# V1.net
KiCad netlist of a schematic drawn in EAGLE
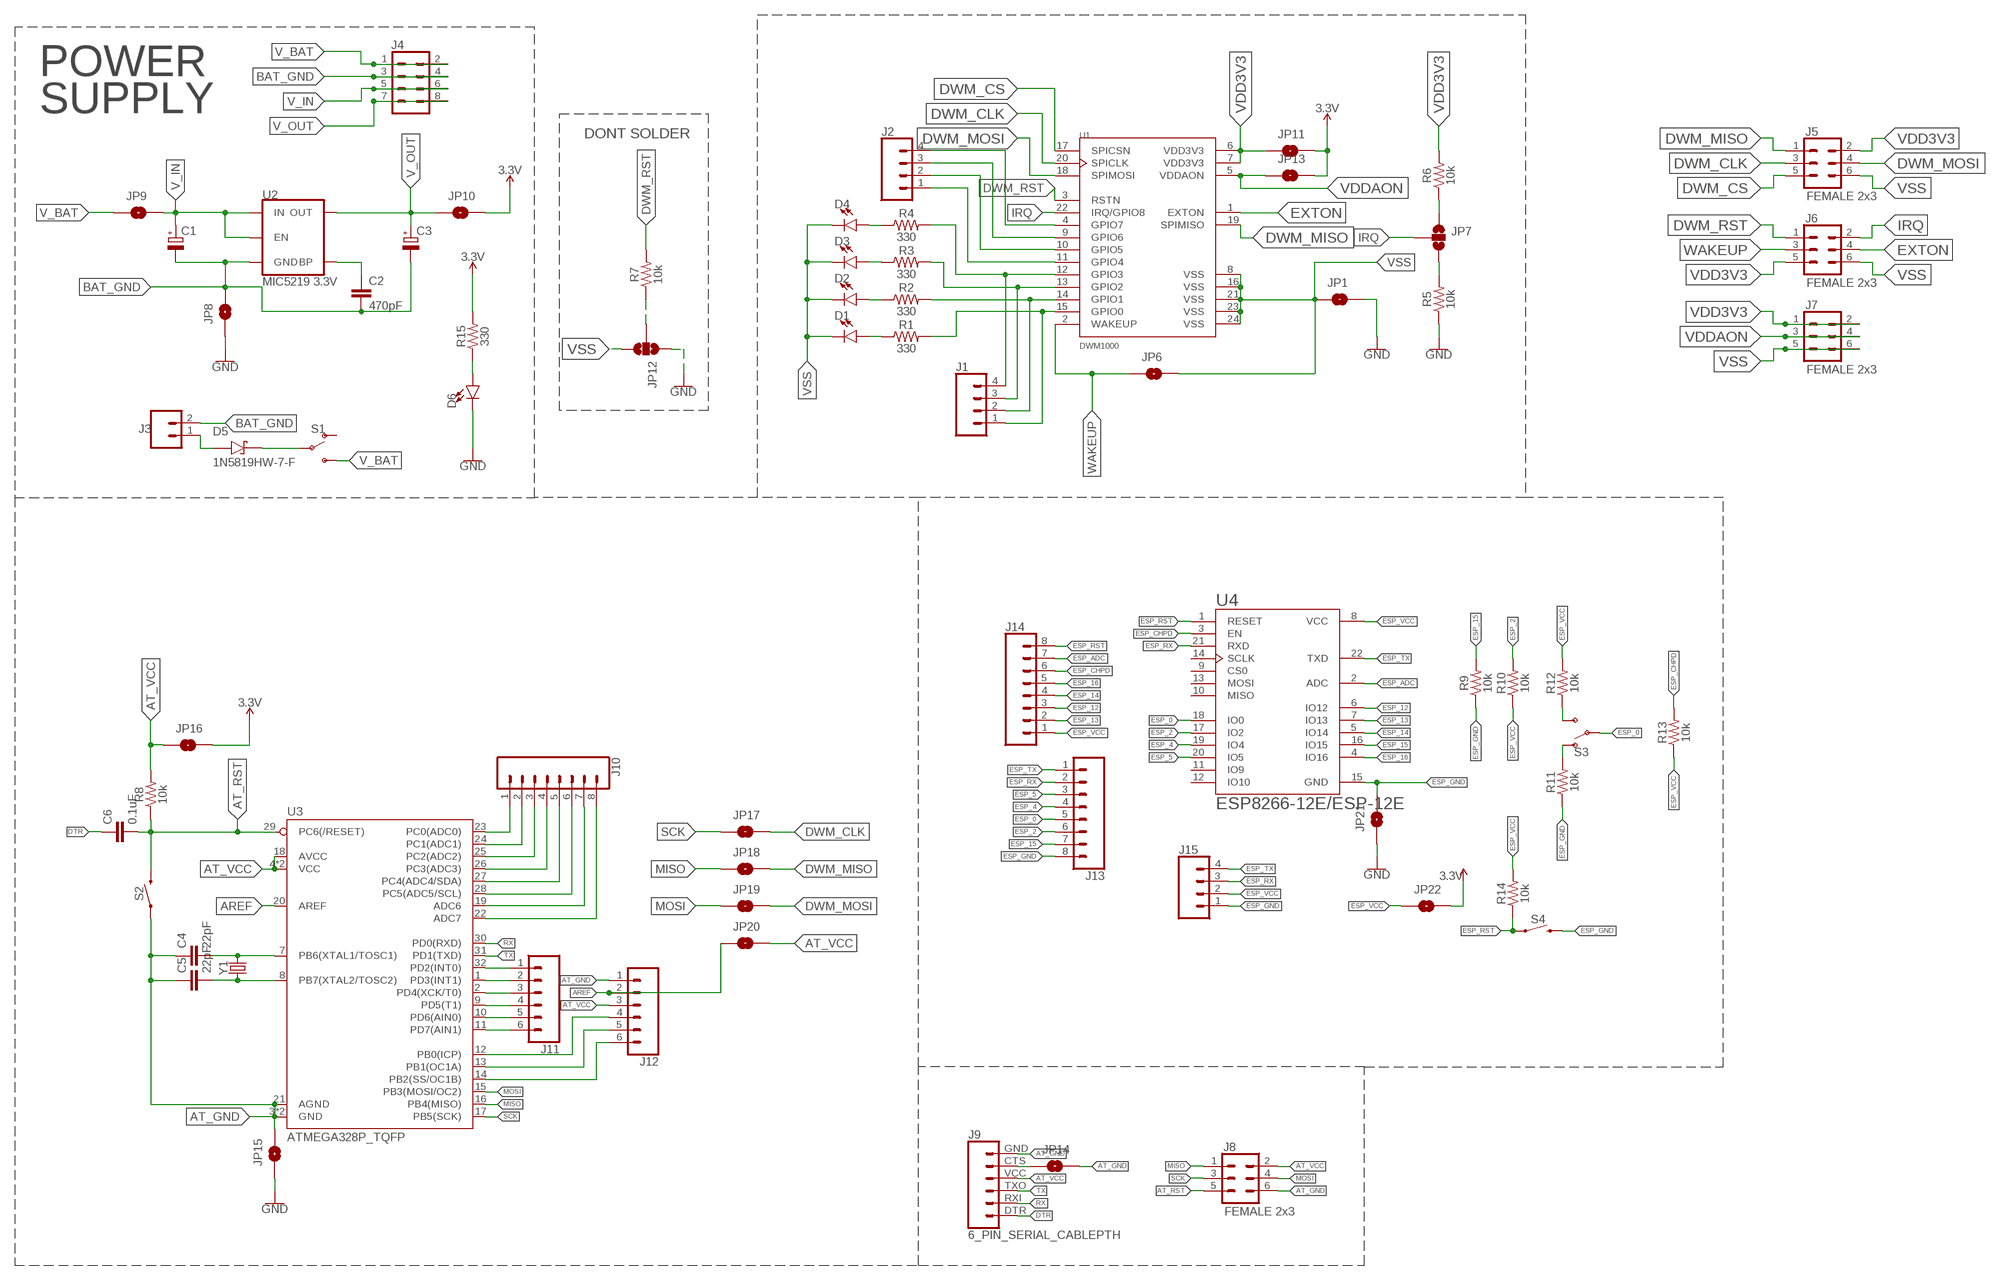
[diagram p0: schematic, sheet 1]

(export (version "E")
  (design (tool "Eeschema 10.0.6"))
  (components
    (comp (ref "C1")
      (value "CPOL-EUSMCA")
      (footprint "eagle-import:SMC_A")
      (libsource (lib "eagle-import") (part "CPOL-EUSMCA"))
    )
    (comp (ref "C2")
      (value "470pF")
      (footprint "eagle-import:0603")
      (libsource (lib "eagle-import") (part "470PF-0603-50V-5%"))
    )
    (comp (ref "C3")
      (value "CPOL-EUSMCA")
      (footprint "eagle-import:SMC_A")
      (libsource (lib "eagle-import") (part "CPOL-EUSMCA"))
    )
    (comp (ref "C4")
      (value "22pF")
      (footprint "eagle-import:0603")
      (libsource (lib "eagle-import") (part "22PF-0603-50V-5%"))
    )
    (comp (ref "C5")
      (value "22pF")
      (footprint "eagle-import:0603")
      (libsource (lib "eagle-import") (part "22PF-0603-50V-5%"))
    )
    (comp (ref "C6")
      (value "0.1uF")
      (footprint "eagle-import:0603")
      (libsource (lib "eagle-import") (part "0.1UF-0603-25V-(+80/-20%)"))
    )
    (comp (ref "D1")
      (value "LED0603")
      (footprint "eagle-import:LED-0603")
      (libsource (lib "eagle-import") (part "LED0603"))
    )
    (comp (ref "D2")
      (value "LED0603")
      (footprint "eagle-import:LED-0603")
      (libsource (lib "eagle-import") (part "LED0603"))
    )
    (comp (ref "D3")
      (value "LED0603")
      (footprint "eagle-import:LED-0603")
      (libsource (lib "eagle-import") (part "LED0603"))
    )
    (comp (ref "D4")
      (value "LED0603")
      (footprint "eagle-import:LED-0603")
      (libsource (lib "eagle-import") (part "LED0603"))
    )
    (comp (ref "D5")
      (value "1N5819HW-7-F")
      (footprint "eagle-import:SOD3715X145N")
      (fields (field (name "MF") "Diodes Inc."))
      (libsource (lib "eagle-import") (part "1N5819HW-7-F"))
    )
    (comp (ref "D6")
      (value "LED0603")
      (footprint "eagle-import:LED-0603")
      (libsource (lib "eagle-import") (part "LED0603"))
    )
    (comp (ref "J1")
      (value "CONN_04")
      (footprint "eagle-import:1X04")
      (libsource (lib "eagle-import") (part "CONN_04"))
    )
    (comp (ref "J2")
      (value "CONN_04")
      (footprint "eagle-import:1X04")
      (libsource (lib "eagle-import") (part "CONN_04"))
    )
    (comp (ref "J3")
      (value "CONN_02")
      (footprint "eagle-import:1X02")
      (libsource (lib "eagle-import") (part "CONN_02"))
    )
    (comp (ref "J4")
      (value "CONN_04X2")
      (footprint "eagle-import:2X4")
      (libsource (lib "eagle-import") (part "CONN_04X2"))
    )
    (comp (ref "J5")
      (value "FEMALE 2x3")
      (footprint "eagle-import:2X3")
      (libsource (lib "eagle-import") (part "CONN_03X2FEMALE"))
    )
    (comp (ref "J6")
      (value "FEMALE 2x3")
      (footprint "eagle-import:2X3")
      (libsource (lib "eagle-import") (part "CONN_03X2FEMALE"))
    )
    (comp (ref "J7")
      (value "FEMALE 2x3")
      (footprint "eagle-import:2X3")
      (libsource (lib "eagle-import") (part "CONN_03X2FEMALE"))
    )
    (comp (ref "J8")
      (value "FEMALE 2x3")
      (footprint "eagle-import:2X3")
      (libsource (lib "eagle-import") (part "CONN_03X2FEMALE"))
    )
    (comp (ref "J9")
      (value "6_PIN_SERIAL_CABLEPTH")
      (footprint "eagle-import:FTDI_BASIC")
      (libsource (lib "eagle-import") (part "6_PIN_SERIAL_CABLEPTH"))
    )
    (comp (ref "J10")
      (value "CONN_08\"")
      (footprint "eagle-import:1X08")
      (libsource (lib "eagle-import") (part "CONN_08{dblquote}"))
    )
    (comp (ref "J11")
      (value "CONN_06SILK_FEMALE_PTH")
      (footprint "eagle-import:1X06")
      (libsource (lib "eagle-import") (part "CONN_06SILK_FEMALE_PTH"))
    )
    (comp (ref "J12")
      (value "CONN_06SILK_FEMALE_PTH")
      (footprint "eagle-import:1X06")
      (libsource (lib "eagle-import") (part "CONN_06SILK_FEMALE_PTH"))
    )
    (comp (ref "J13")
      (value "CONN_08\"")
      (footprint "eagle-import:1X08")
      (libsource (lib "eagle-import") (part "CONN_08{dblquote}"))
    )
    (comp (ref "J14")
      (value "CONN_08\"")
      (footprint "eagle-import:1X08")
      (libsource (lib "eagle-import") (part "CONN_08{dblquote}"))
    )
    (comp (ref "J15")
      (value "CONN_04")
      (footprint "eagle-import:1X04")
      (libsource (lib "eagle-import") (part "CONN_04"))
    )
    (comp (ref "JP1")
      (value "JUMPER-SMT_2_NO_NO-SILK")
      (footprint "eagle-import:SMT-JUMPER_2_NO_NO-SILK")
      (libsource (lib "eagle-import") (part "JUMPER-SMT_2_NO_NO-SILK"))
    )
    (comp (ref "JP6")
      (value "JUMPER-SMT_2_NO_NO-SILK")
      (footprint "eagle-import:SMT-JUMPER_2_NO_NO-SILK")
      (libsource (lib "eagle-import") (part "JUMPER-SMT_2_NO_NO-SILK"))
    )
    (comp (ref "JP7")
      (value "JUMPER-SMT_3_NO_NO_SILK")
      (footprint "eagle-import:SMT-JUMPER_3_0-NO_TRACE_NO-SILK")
      (libsource (lib "eagle-import") (part "JUMPER-SMT_3_NO_NO_SILK"))
    )
    (comp (ref "JP8")
      (value "JUMPER-SMT_2_NO_NO-SILK")
      (footprint "eagle-import:SMT-JUMPER_2_NO_NO-SILK")
      (libsource (lib "eagle-import") (part "JUMPER-SMT_2_NO_NO-SILK"))
    )
    (comp (ref "JP9")
      (value "JUMPER-SMT_2_NO_NO-SILK")
      (footprint "eagle-import:SMT-JUMPER_2_NO_NO-SILK")
      (libsource (lib "eagle-import") (part "JUMPER-SMT_2_NO_NO-SILK"))
    )
    (comp (ref "JP10")
      (value "JUMPER-SMT_2_NO_NO-SILK")
      (footprint "eagle-import:SMT-JUMPER_2_NO_NO-SILK")
      (libsource (lib "eagle-import") (part "JUMPER-SMT_2_NO_NO-SILK"))
    )
    (comp (ref "JP11")
      (value "JUMPER-SMT_2_NO_NO-SILK")
      (footprint "eagle-import:SMT-JUMPER_2_NO_NO-SILK")
      (libsource (lib "eagle-import") (part "JUMPER-SMT_2_NO_NO-SILK"))
    )
    (comp (ref "JP12")
      (value "JUMPER-SMT_3_NO_NO_SILK")
      (footprint "eagle-import:SMT-JUMPER_3_0-NO_TRACE_NO-SILK")
      (libsource (lib "eagle-import") (part "JUMPER-SMT_3_NO_NO_SILK"))
    )
    (comp (ref "JP13")
      (value "JUMPER-SMT_2_NO_NO-SILK")
      (footprint "eagle-import:SMT-JUMPER_2_NO_NO-SILK")
      (libsource (lib "eagle-import") (part "JUMPER-SMT_2_NO_NO-SILK"))
    )
    (comp (ref "JP14")
      (value "JUMPER-SMT_2_NO_NO-SILK")
      (footprint "eagle-import:SMT-JUMPER_2_NO_NO-SILK")
      (libsource (lib "eagle-import") (part "JUMPER-SMT_2_NO_NO-SILK"))
    )
    (comp (ref "JP15")
      (value "JUMPER-SMT_2_NO_NO-SILK")
      (footprint "eagle-import:SMT-JUMPER_2_NO_NO-SILK")
      (libsource (lib "eagle-import") (part "JUMPER-SMT_2_NO_NO-SILK"))
    )
    (comp (ref "JP16")
      (value "JUMPER-SMT_2_NO_NO-SILK")
      (footprint "eagle-import:SMT-JUMPER_2_NO_NO-SILK")
      (libsource (lib "eagle-import") (part "JUMPER-SMT_2_NO_NO-SILK"))
    )
    (comp (ref "JP17")
      (value "JUMPER-SMT_2_NO_NO-SILK")
      (footprint "eagle-import:SMT-JUMPER_2_NO_NO-SILK")
      (libsource (lib "eagle-import") (part "JUMPER-SMT_2_NO_NO-SILK"))
    )
    (comp (ref "JP18")
      (value "JUMPER-SMT_2_NO_NO-SILK")
      (footprint "eagle-import:SMT-JUMPER_2_NO_NO-SILK")
      (libsource (lib "eagle-import") (part "JUMPER-SMT_2_NO_NO-SILK"))
    )
    (comp (ref "JP19")
      (value "JUMPER-SMT_2_NO_NO-SILK")
      (footprint "eagle-import:SMT-JUMPER_2_NO_NO-SILK")
      (libsource (lib "eagle-import") (part "JUMPER-SMT_2_NO_NO-SILK"))
    )
    (comp (ref "JP20")
      (value "JUMPER-SMT_2_NO_NO-SILK")
      (footprint "eagle-import:SMT-JUMPER_2_NO_NO-SILK")
      (libsource (lib "eagle-import") (part "JUMPER-SMT_2_NO_NO-SILK"))
    )
    (comp (ref "JP21")
      (value "JUMPER-SMT_2_NO_NO-SILK")
      (footprint "eagle-import:SMT-JUMPER_2_NO_NO-SILK")
      (libsource (lib "eagle-import") (part "JUMPER-SMT_2_NO_NO-SILK"))
    )
    (comp (ref "JP22")
      (value "JUMPER-SMT_2_NO_NO-SILK")
      (footprint "eagle-import:SMT-JUMPER_2_NO_NO-SILK")
      (libsource (lib "eagle-import") (part "JUMPER-SMT_2_NO_NO-SILK"))
    )
    (comp (ref "R1")
      (value "330")
      (footprint "eagle-import:0603")
      (libsource (lib "eagle-import") (part "330OHM-0603-1/10W-1%"))
    )
    (comp (ref "R2")
      (value "330")
      (footprint "eagle-import:0603")
      (libsource (lib "eagle-import") (part "330OHM-0603-1/10W-1%"))
    )
    (comp (ref "R3")
      (value "330")
      (footprint "eagle-import:0603")
      (libsource (lib "eagle-import") (part "330OHM-0603-1/10W-1%"))
    )
    (comp (ref "R4")
      (value "330")
      (footprint "eagle-import:0603")
      (libsource (lib "eagle-import") (part "330OHM-0603-1/10W-1%"))
    )
    (comp (ref "R5")
      (value "10k")
      (footprint "eagle-import:0603")
      (libsource (lib "eagle-import") (part "10KOHM-0603-1/10W-1%"))
    )
    (comp (ref "R6")
      (value "10k")
      (footprint "eagle-import:0603")
      (libsource (lib "eagle-import") (part "10KOHM-0603-1/10W-1%"))
    )
    (comp (ref "R7")
      (value "10k")
      (footprint "eagle-import:0603")
      (libsource (lib "eagle-import") (part "10KOHM-0603-1/10W-1%"))
    )
    (comp (ref "R8")
      (value "10k")
      (footprint "eagle-import:0603")
      (libsource (lib "eagle-import") (part "10KOHM-0603-1/10W-1%"))
    )
    (comp (ref "R9")
      (value "10k")
      (footprint "eagle-import:0603")
      (libsource (lib "eagle-import") (part "10KOHM-0603-1/10W-1%"))
    )
    (comp (ref "R10")
      (value "10k")
      (footprint "eagle-import:0603")
      (libsource (lib "eagle-import") (part "10KOHM-0603-1/10W-1%"))
    )
    (comp (ref "R11")
      (value "10k")
      (footprint "eagle-import:0603")
      (libsource (lib "eagle-import") (part "10KOHM-0603-1/10W-1%"))
    )
    (comp (ref "R12")
      (value "10k")
      (footprint "eagle-import:0603")
      (libsource (lib "eagle-import") (part "10KOHM-0603-1/10W-1%"))
    )
    (comp (ref "R13")
      (value "10k")
      (footprint "eagle-import:0603")
      (libsource (lib "eagle-import") (part "10KOHM-0603-1/10W-1%"))
    )
    (comp (ref "R14")
      (value "10k")
      (footprint "eagle-import:0603")
      (libsource (lib "eagle-import") (part "10KOHM-0603-1/10W-1%"))
    )
    (comp (ref "R15")
      (value "330")
      (footprint "eagle-import:0603")
      (libsource (lib "eagle-import") (part "330OHM-0603-1/10W-1%"))
    )
    (comp (ref "S1")
      (value "SWITCH-SPDT-SMD-AYZ0202")
      (footprint "eagle-import:SWITCH_DPDT_SMD_AYZ0202")
      (libsource (lib "eagle-import") (part "SWITCH-SPDT-SMD-AYZ0202"))
    )
    (comp (ref "S2")
      (value "MOMENTARY-SWITCH-SPST-SMD-6.0X3.5MM")
      (footprint "eagle-import:TACTILE_SWITCH_SMD_6.0X3.5MM")
      (libsource (lib "eagle-import") (part "MOMENTARY-SWITCH-SPST-SMD-6.0X3.5MM"))
    )
    (comp (ref "S3")
      (value "SWITCH-SPDT-SMD-AYZ0202")
      (footprint "eagle-import:SWITCH_DPDT_SMD_AYZ0202")
      (libsource (lib "eagle-import") (part "SWITCH-SPDT-SMD-AYZ0202"))
    )
    (comp (ref "S4")
      (value "MOMENTARY-SWITCH-SPST-SMD-6.0X3.5MM")
      (footprint "eagle-import:TACTILE_SWITCH_SMD_6.0X3.5MM")
      (libsource (lib "eagle-import") (part "MOMENTARY-SWITCH-SPST-SMD-6.0X3.5MM"))
    )
    (comp (ref "U1")
      (value "DWM1000")
      (footprint "eagle-import:XCVR_DWM1000")
      (fields (field (name "MF") "Decawave Limited"))
      (libsource (lib "eagle-import") (part "DWM1000"))
    )
    (comp (ref "U2")
      (value "MIC5219 3.3V")
      (footprint "eagle-import:SOT23-5")
      (libsource (lib "eagle-import") (part "V_REG_MIC52193.3V"))
    )
    (comp (ref "U3")
      (value "ATMEGA328P_TQFP")
      (footprint "eagle-import:TQFP32-08")
      (libsource (lib "eagle-import") (part "ATMEGA328P_TQFP"))
    )
    (comp (ref "U4")
      (value "ESP8266-12E/ESP-12E")
      (footprint "eagle-import:XCVR_ESP8266-12E_ESP-12E")
      (fields (field (name "MF") "AI-Thinker"))
      (libsource (lib "eagle-import") (part "ESP8266-12E/ESP-12E"))
    )
    (comp (ref "Y1")
      (value "CRYSTALSMD-HC49UP")
      (footprint "eagle-import:HC49UP")
      (libsource (lib "eagle-import") (part "CRYSTALSMD-HC49UP"))
    )
  )
  (nets
    (net (code "1") (name "3.3V") (class "Default")
      (node (ref "JP10") (pin "2") (pinfunction "2_2") (pintype "passive"))
      (node (ref "JP11") (pin "2") (pinfunction "2_2") (pintype "passive"))
      (node (ref "JP13") (pin "2") (pinfunction "2_2") (pintype "passive"))
      (node (ref "JP16") (pin "2") (pinfunction "2_2") (pintype "passive"))
      (node (ref "JP22") (pin "2") (pinfunction "2_2") (pintype "passive"))
      (node (ref "R15") (pin "2") (pinfunction "2_2") (pintype "passive"))
    )
    (net (code "2") (name "AREF") (class "Default")
      (node (ref "J12") (pin "2") (pinfunction "2_2") (pintype "passive"))
      (node (ref "JP20") (pin "1") (pinfunction "1_1") (pintype "passive"))
      (node (ref "U3") (pin "20") (pinfunction "AREF_20") (pintype "bidirectional"))
    )
    (net (code "3") (name "AT_GND") (class "Default")
      (node (ref "C4") (pin "1") (pinfunction "1_1") (pintype "passive"))
      (node (ref "C5") (pin "1") (pinfunction "1_1") (pintype "passive"))
      (node (ref "J12") (pin "1") (pinfunction "1_1") (pintype "passive"))
      (node (ref "J8") (pin "6") (pinfunction "6_6") (pintype "bidirectional"))
      (node (ref "J9") (pin "GND") (pinfunction "6_GND") (pintype "passive"))
      (node (ref "JP14") (pin "2") (pinfunction "2_2") (pintype "passive"))
      (node (ref "JP15") (pin "2") (pinfunction "2_2") (pintype "passive"))
      (node (ref "S2") (pin "1") (pinfunction "1_1") (pintype "passive"))
      (node (ref "U3") (pin "21") (pinfunction "AGND_21") (pintype "bidirectional"))
      (node (ref "U3") (pin "3") (pinfunction "GND_3") (pintype "bidirectional"))
      (node (ref "U3") (pin "5") (pinfunction "GND_5") (pintype "bidirectional"))
    )
    (net (code "4") (name "AT_RST") (class "Default")
      (node (ref "C6") (pin "2") (pinfunction "2_2") (pintype "passive"))
      (node (ref "J8") (pin "5") (pinfunction "5_5") (pintype "bidirectional"))
      (node (ref "R8") (pin "1") (pinfunction "1_1") (pintype "passive"))
      (node (ref "S2") (pin "2") (pinfunction "2_2") (pintype "passive"))
      (node (ref "U3") (pin "29") (pinfunction "PC6(/RESET)_29") (pintype "bidirectional"))
    )
    (net (code "5") (name "AT_VCC") (class "Default")
      (node (ref "J12") (pin "3") (pinfunction "3_3") (pintype "passive"))
      (node (ref "J8") (pin "2") (pinfunction "2_2") (pintype "bidirectional"))
      (node (ref "J9") (pin "VCC") (pinfunction "4_VCC") (pintype "passive"))
      (node (ref "JP16") (pin "1") (pinfunction "1_1") (pintype "passive"))
      (node (ref "JP20") (pin "2") (pinfunction "2_2") (pintype "passive"))
      (node (ref "R8") (pin "2") (pinfunction "2_2") (pintype "passive"))
      (node (ref "U3") (pin "18") (pinfunction "AVCC_18") (pintype "bidirectional"))
      (node (ref "U3") (pin "4") (pinfunction "VCC_4") (pintype "bidirectional"))
      (node (ref "U3") (pin "6") (pinfunction "VCC_6") (pintype "bidirectional"))
    )
    (net (code "6") (name "BAT_GND") (class "Default")
      (node (ref "C1") (pin "-") (pinfunction "-_-") (pintype "passive"))
      (node (ref "C2") (pin "2") (pinfunction "2_2") (pintype "passive"))
      (node (ref "C3") (pin "-") (pinfunction "-_-") (pintype "passive"))
      (node (ref "J3") (pin "2") (pinfunction "2_2") (pintype "passive"))
      (node (ref "J4") (pin "3") (pinfunction "3_3") (pintype "passive"))
      (node (ref "J4") (pin "4") (pinfunction "4_4") (pintype "passive"))
      (node (ref "JP8") (pin "2") (pinfunction "2_2") (pintype "passive"))
      (node (ref "U2") (pin "2") (pinfunction "GND_2") (pintype "input"))
    )
    (net (code "7") (name "DTR") (class "Default")
      (node (ref "C6") (pin "1") (pinfunction "1_1") (pintype "passive"))
      (node (ref "J9") (pin "DTR") (pinfunction "1_DTR") (pintype "passive"))
    )
    (net (code "8") (name "DWM_CLK") (class "Default")
      (node (ref "J5") (pin "3") (pinfunction "3_3") (pintype "bidirectional"))
      (node (ref "JP17") (pin "2") (pinfunction "2_2") (pintype "passive"))
      (node (ref "U1") (pin "20") (pinfunction "SPICLK_20") (pintype "input"))
    )
    (net (code "9") (name "DWM_CS") (class "Default")
      (node (ref "J5") (pin "5") (pinfunction "5_5") (pintype "bidirectional"))
      (node (ref "U1") (pin "17") (pinfunction "SPICSN_17") (pintype "input"))
    )
    (net (code "10") (name "DWM_MISO") (class "Default")
      (node (ref "J5") (pin "1") (pinfunction "1_1") (pintype "bidirectional"))
      (node (ref "JP18") (pin "2") (pinfunction "2_2") (pintype "passive"))
      (node (ref "U1") (pin "19") (pinfunction "SPIMISO_19") (pintype "output"))
    )
    (net (code "11") (name "DWM_MOSI") (class "Default")
      (node (ref "J5") (pin "4") (pinfunction "4_4") (pintype "bidirectional"))
      (node (ref "JP19") (pin "2") (pinfunction "2_2") (pintype "passive"))
      (node (ref "U1") (pin "18") (pinfunction "SPIMOSI_18") (pintype "input"))
    )
    (net (code "12") (name "DWM_RST") (class "Default")
      (node (ref "J6") (pin "1") (pinfunction "1_1") (pintype "bidirectional"))
      (node (ref "R7") (pin "2") (pinfunction "2_2") (pintype "passive"))
      (node (ref "U1") (pin "3") (pinfunction "RSTN_3") (pintype "bidirectional"))
    )
    (net (code "13") (name "ESP_0") (class "Default")
      (node (ref "J13") (pin "5") (pinfunction "5_5") (pintype "passive"))
      (node (ref "S3") (pin "2") (pinfunction "P_2") (pintype "passive"))
      (node (ref "U4") (pin "18") (pinfunction "IO0_18") (pintype "bidirectional"))
    )
    (net (code "14") (name "ESP_2") (class "Default")
      (node (ref "J13") (pin "6") (pinfunction "6_6") (pintype "passive"))
      (node (ref "R10") (pin "2") (pinfunction "2_2") (pintype "passive"))
      (node (ref "U4") (pin "17") (pinfunction "IO2_17") (pintype "bidirectional"))
    )
    (net (code "15") (name "ESP_4") (class "Default")
      (node (ref "J13") (pin "4") (pinfunction "4_4") (pintype "passive"))
      (node (ref "U4") (pin "19") (pinfunction "IO4_19") (pintype "bidirectional"))
    )
    (net (code "16") (name "ESP_5") (class "Default")
      (node (ref "J13") (pin "3") (pinfunction "3_3") (pintype "passive"))
      (node (ref "U4") (pin "20") (pinfunction "IO5_20") (pintype "bidirectional"))
    )
    (net (code "17") (name "ESP_12") (class "Default")
      (node (ref "J14") (pin "3") (pinfunction "3_3") (pintype "passive"))
      (node (ref "U4") (pin "6") (pinfunction "IO12_6") (pintype "bidirectional"))
    )
    (net (code "18") (name "ESP_13") (class "Default")
      (node (ref "J14") (pin "2") (pinfunction "2_2") (pintype "passive"))
      (node (ref "U4") (pin "7") (pinfunction "IO13_7") (pintype "bidirectional"))
    )
    (net (code "19") (name "ESP_14") (class "Default")
      (node (ref "J14") (pin "4") (pinfunction "4_4") (pintype "passive"))
      (node (ref "U4") (pin "5") (pinfunction "IO14_5") (pintype "bidirectional"))
    )
    (net (code "20") (name "ESP_15") (class "Default")
      (node (ref "J13") (pin "7") (pinfunction "7_7") (pintype "passive"))
      (node (ref "R9") (pin "2") (pinfunction "2_2") (pintype "passive"))
      (node (ref "U4") (pin "16") (pinfunction "IO15_16") (pintype "bidirectional"))
    )
    (net (code "21") (name "ESP_16") (class "Default")
      (node (ref "J14") (pin "5") (pinfunction "5_5") (pintype "passive"))
      (node (ref "U4") (pin "4") (pinfunction "IO16_4") (pintype "bidirectional"))
    )
    (net (code "22") (name "ESP_ADC") (class "Default")
      (node (ref "J14") (pin "7") (pinfunction "7_7") (pintype "passive"))
      (node (ref "U4") (pin "2") (pinfunction "ADC_2") (pintype "passive"))
    )
    (net (code "23") (name "ESP_CHPD") (class "Default")
      (node (ref "J14") (pin "6") (pinfunction "6_6") (pintype "passive"))
      (node (ref "R13") (pin "2") (pinfunction "2_2") (pintype "passive"))
      (node (ref "U4") (pin "3") (pinfunction "EN_3") (pintype "input"))
    )
    (net (code "24") (name "ESP_GND") (class "Default")
      (node (ref "J13") (pin "8") (pinfunction "8_8") (pintype "passive"))
      (node (ref "J15") (pin "1") (pinfunction "1_1") (pintype "passive"))
      (node (ref "JP21") (pin "2") (pinfunction "2_2") (pintype "passive"))
      (node (ref "R11") (pin "1") (pinfunction "1_1") (pintype "passive"))
      (node (ref "R9") (pin "1") (pinfunction "1_1") (pintype "passive"))
      (node (ref "S4") (pin "2") (pinfunction "2_2") (pintype "passive"))
      (node (ref "U4") (pin "15") (pinfunction "GND_15") (pintype "power_in"))
    )
    (net (code "25") (name "ESP_RST") (class "Default")
      (node (ref "J14") (pin "8") (pinfunction "8_8") (pintype "passive"))
      (node (ref "R14") (pin "1") (pinfunction "1_1") (pintype "passive"))
      (node (ref "S4") (pin "1") (pinfunction "1_1") (pintype "passive"))
      (node (ref "U4") (pin "1") (pinfunction "RESET_1") (pintype "input"))
    )
    (net (code "26") (name "ESP_RX") (class "Default")
      (node (ref "J13") (pin "2") (pinfunction "2_2") (pintype "passive"))
      (node (ref "J15") (pin "3") (pinfunction "3_3") (pintype "passive"))
      (node (ref "U4") (pin "21") (pinfunction "RXD_21") (pintype "input"))
    )
    (net (code "27") (name "ESP_TX") (class "Default")
      (node (ref "J13") (pin "1") (pinfunction "1_1") (pintype "passive"))
      (node (ref "J15") (pin "4") (pinfunction "4_4") (pintype "passive"))
      (node (ref "U4") (pin "22") (pinfunction "TXD_22") (pintype "output"))
    )
    (net (code "28") (name "ESP_VCC") (class "Default")
      (node (ref "J14") (pin "1") (pinfunction "1_1") (pintype "passive"))
      (node (ref "J15") (pin "2") (pinfunction "2_2") (pintype "passive"))
      (node (ref "JP22") (pin "1") (pinfunction "1_1") (pintype "passive"))
      (node (ref "R10") (pin "1") (pinfunction "1_1") (pintype "passive"))
      (node (ref "R12") (pin "2") (pinfunction "2_2") (pintype "passive"))
      (node (ref "R13") (pin "1") (pinfunction "1_1") (pintype "passive"))
      (node (ref "R14") (pin "2") (pinfunction "2_2") (pintype "passive"))
      (node (ref "U4") (pin "8") (pinfunction "VCC_8") (pintype "power_in"))
    )
    (net (code "29") (name "EXTON") (class "Default")
      (node (ref "J6") (pin "4") (pinfunction "4_4") (pintype "bidirectional"))
      (node (ref "U1") (pin "1") (pinfunction "EXTON_1") (pintype "output"))
    )
    (net (code "30") (name "GND") (class "Default")
      (node (ref "D6") (pin "C") (pinfunction "C_C") (pintype "passive"))
      (node (ref "JP1") (pin "2") (pinfunction "2_2") (pintype "passive"))
      (node (ref "JP12") (pin "1") (pinfunction "1_1") (pintype "passive"))
      (node (ref "JP15") (pin "1") (pinfunction "1_1") (pintype "passive"))
      (node (ref "JP21") (pin "1") (pinfunction "1_1") (pintype "passive"))
      (node (ref "JP8") (pin "1") (pinfunction "1_1") (pintype "passive"))
      (node (ref "R5") (pin "1") (pinfunction "1_1") (pintype "passive"))
    )
    (net (code "31") (name "IRQ") (class "Default")
      (node (ref "J6") (pin "2") (pinfunction "2_2") (pintype "bidirectional"))
      (node (ref "JP7") (pin "2") (pinfunction "2_2") (pintype "passive"))
      (node (ref "U1") (pin "22") (pinfunction "IRQ/GPIO8_22") (pintype "bidirectional"))
    )
    (net (code "32") (name "MISO") (class "Default")
      (node (ref "J8") (pin "1") (pinfunction "1_1") (pintype "bidirectional"))
      (node (ref "JP18") (pin "1") (pinfunction "1_1") (pintype "passive"))
      (node (ref "U3") (pin "16") (pinfunction "PB4(MISO)_16") (pintype "bidirectional"))
    )
    (net (code "33") (name "MOSI") (class "Default")
      (node (ref "J8") (pin "4") (pinfunction "4_4") (pintype "bidirectional"))
      (node (ref "JP19") (pin "1") (pinfunction "1_1") (pintype "passive"))
      (node (ref "U3") (pin "15") (pinfunction "PB3(MOSI/OC2)_15") (pintype "bidirectional"))
    )
    (net (code "34") (name "Net-(D1-PadA)") (class "Default")
      (node (ref "D1") (pin "A") (pinfunction "A_A") (pintype "passive"))
      (node (ref "R1") (pin "1") (pinfunction "1_1") (pintype "passive"))
    )
    (net (code "35") (name "Net-(D2-PadA)") (class "Default")
      (node (ref "D2") (pin "A") (pinfunction "A_A") (pintype "passive"))
      (node (ref "R2") (pin "1") (pinfunction "1_1") (pintype "passive"))
    )
    (net (code "36") (name "Net-(D3-PadA)") (class "Default")
      (node (ref "D3") (pin "A") (pinfunction "A_A") (pintype "passive"))
      (node (ref "R3") (pin "1") (pinfunction "1_1") (pintype "passive"))
    )
    (net (code "37") (name "Net-(D4-PadA)") (class "Default")
      (node (ref "D4") (pin "A") (pinfunction "A_A") (pintype "passive"))
      (node (ref "R4") (pin "1") (pinfunction "1_1") (pintype "passive"))
    )
    (net (code "38") (name "Net-(D5-K)") (class "Default")
      (node (ref "D5") (pin "C") (pinfunction "K_C") (pintype "passive"))
      (node (ref "S1") (pin "2") (pinfunction "P_2") (pintype "passive"))
    )
    (net (code "39") (name "Net-(D5-PadA)") (class "Default")
      (node (ref "D5") (pin "A") (pinfunction "A_A") (pintype "passive"))
      (node (ref "J3") (pin "1") (pinfunction "1_1") (pintype "passive"))
    )
    (net (code "40") (name "Net-(D6-PadA)") (class "Default")
      (node (ref "D6") (pin "A") (pinfunction "A_A") (pintype "passive"))
      (node (ref "R15") (pin "1") (pinfunction "1_1") (pintype "passive"))
    )
    (net (code "41") (name "Net-(J9-5)") (class "Default")
      (node (ref "J9") (pin "CTS") (pinfunction "5_CTS") (pintype "passive"))
      (node (ref "JP14") (pin "1") (pinfunction "1_1") (pintype "passive"))
    )
    (net (code "42") (name "Net-(JP7-Pad1)") (class "Default")
      (node (ref "JP7") (pin "1") (pinfunction "1_1") (pintype "passive"))
      (node (ref "R6") (pin "1") (pinfunction "1_1") (pintype "passive"))
    )
    (net (code "43") (name "Net-(JP7-Pad3)") (class "Default")
      (node (ref "JP7") (pin "3") (pinfunction "3_3") (pintype "passive"))
      (node (ref "R5") (pin "2") (pinfunction "2_2") (pintype "passive"))
    )
    (net (code "44") (name "Net-(JP12-Pad2)") (class "Default")
      (node (ref "JP12") (pin "2") (pinfunction "2_2") (pintype "passive"))
      (node (ref "R7") (pin "1") (pinfunction "1_1") (pintype "passive"))
    )
    (net (code "45") (name "Net-(S3-O)") (class "Default")
      (node (ref "R11") (pin "2") (pinfunction "2_2") (pintype "passive"))
      (node (ref "S3") (pin "1") (pinfunction "O_1") (pintype "passive"))
    )
    (net (code "46") (name "Net-(S3-S)") (class "Default")
      (node (ref "R12") (pin "1") (pinfunction "1_1") (pintype "passive"))
      (node (ref "S3") (pin "3") (pinfunction "S_3") (pintype "passive"))
    )
    (net (code "47") (name "Net-(U1-GPIO0)") (class "Default")
      (node (ref "J1") (pin "1") (pinfunction "1_1") (pintype "passive"))
      (node (ref "R1") (pin "2") (pinfunction "2_2") (pintype "passive"))
      (node (ref "U1") (pin "15") (pinfunction "GPIO0_15") (pintype "bidirectional"))
    )
    (net (code "48") (name "Net-(U1-GPIO1)") (class "Default")
      (node (ref "J1") (pin "2") (pinfunction "2_2") (pintype "passive"))
      (node (ref "R2") (pin "2") (pinfunction "2_2") (pintype "passive"))
      (node (ref "U1") (pin "14") (pinfunction "GPIO1_14") (pintype "bidirectional"))
    )
    (net (code "49") (name "Net-(U1-GPIO2)") (class "Default")
      (node (ref "J1") (pin "3") (pinfunction "3_3") (pintype "passive"))
      (node (ref "R3") (pin "2") (pinfunction "2_2") (pintype "passive"))
      (node (ref "U1") (pin "13") (pinfunction "GPIO2_13") (pintype "bidirectional"))
    )
    (net (code "50") (name "Net-(U1-GPIO3)") (class "Default")
      (node (ref "J1") (pin "4") (pinfunction "4_4") (pintype "passive"))
      (node (ref "R4") (pin "2") (pinfunction "2_2") (pintype "passive"))
      (node (ref "U1") (pin "12") (pinfunction "GPIO3_12") (pintype "bidirectional"))
    )
    (net (code "51") (name "Net-(U1-GPIO4)") (class "Default")
      (node (ref "J2") (pin "1") (pinfunction "1_1") (pintype "passive"))
      (node (ref "U1") (pin "11") (pinfunction "GPIO4_11") (pintype "bidirectional"))
    )
    (net (code "52") (name "Net-(U1-GPIO5)") (class "Default")
      (node (ref "J2") (pin "2") (pinfunction "2_2") (pintype "passive"))
      (node (ref "U1") (pin "10") (pinfunction "GPIO5_10") (pintype "bidirectional"))
    )
    (net (code "53") (name "Net-(U1-GPIO6)") (class "Default")
      (node (ref "J2") (pin "3") (pinfunction "3_3") (pintype "passive"))
      (node (ref "U1") (pin "9") (pinfunction "GPIO6_9") (pintype "bidirectional"))
    )
    (net (code "54") (name "Net-(U1-GPIO7)") (class "Default")
      (node (ref "J2") (pin "4") (pinfunction "4_4") (pintype "passive"))
      (node (ref "U1") (pin "4") (pinfunction "GPIO7_4") (pintype "bidirectional"))
    )
    (net (code "55") (name "Net-(U2-BP)") (class "Default")
      (node (ref "C2") (pin "1") (pinfunction "1_1") (pintype "passive"))
      (node (ref "U2") (pin "4") (pinfunction "BP_4") (pintype "input"))
    )
    (net (code "56") (name "Net-(U3-ADC6)") (class "Default")
      (node (ref "J10") (pin "7") (pinfunction "7_7") (pintype "passive"))
      (node (ref "U3") (pin "19") (pinfunction "ADC6_19") (pintype "bidirectional"))
    )
    (net (code "57") (name "Net-(U3-ADC7)") (class "Default")
      (node (ref "J10") (pin "8") (pinfunction "8_8") (pintype "passive"))
      (node (ref "U3") (pin "22") (pinfunction "ADC7_22") (pintype "bidirectional"))
    )
    (net (code "58") (name "Net-(U3-PB0(ICP))") (class "Default")
      (node (ref "J12") (pin "4") (pinfunction "4_4") (pintype "passive"))
      (node (ref "U3") (pin "12") (pinfunction "PB0(ICP)_12") (pintype "bidirectional"))
    )
    (net (code "59") (name "Net-(U3-PB1(OC1A))") (class "Default")
      (node (ref "J12") (pin "5") (pinfunction "5_5") (pintype "passive"))
      (node (ref "U3") (pin "13") (pinfunction "PB1(OC1A)_13") (pintype "bidirectional"))
    )
    (net (code "60") (name "Net-(U3-PB2(SS{slash}OC1B))") (class "Default")
      (node (ref "J12") (pin "6") (pinfunction "6_6") (pintype "passive"))
      (node (ref "U3") (pin "14") (pinfunction "PB2(SS/OC1B)_14") (pintype "bidirectional"))
    )
    (net (code "61") (name "Net-(U3-PB6(XTAL1{slash}TOSC1))") (class "Default")
      (node (ref "C4") (pin "2") (pinfunction "2_2") (pintype "passive"))
      (node (ref "U3") (pin "7") (pinfunction "PB6(XTAL1/TOSC1)_7") (pintype "bidirectional"))
      (node (ref "Y1") (pin "2") (pinfunction "2_2") (pintype "passive"))
    )
    (net (code "62") (name "Net-(U3-PB7(XTAL2{slash}TOSC2))") (class "Default")
      (node (ref "C5") (pin "2") (pinfunction "2_2") (pintype "passive"))
      (node (ref "U3") (pin "8") (pinfunction "PB7(XTAL2/TOSC2)_8") (pintype "bidirectional"))
      (node (ref "Y1") (pin "1") (pinfunction "1_1") (pintype "passive"))
    )
    (net (code "63") (name "Net-(U3-PC0(ADC0))") (class "Default")
      (node (ref "J10") (pin "1") (pinfunction "1_1") (pintype "passive"))
      (node (ref "U3") (pin "23") (pinfunction "PC0(ADC0)_23") (pintype "bidirectional"))
    )
    (net (code "64") (name "Net-(U3-PC1(ADC1))") (class "Default")
      (node (ref "J10") (pin "2") (pinfunction "2_2") (pintype "passive"))
      (node (ref "U3") (pin "24") (pinfunction "PC1(ADC1)_24") (pintype "bidirectional"))
    )
    (net (code "65") (name "Net-(U3-PC2(ADC2))") (class "Default")
      (node (ref "J10") (pin "3") (pinfunction "3_3") (pintype "passive"))
      (node (ref "U3") (pin "25") (pinfunction "PC2(ADC2)_25") (pintype "bidirectional"))
    )
    (net (code "66") (name "Net-(U3-PC3(ADC3))") (class "Default")
      (node (ref "J10") (pin "4") (pinfunction "4_4") (pintype "passive"))
      (node (ref "U3") (pin "26") (pinfunction "PC3(ADC3)_26") (pintype "bidirectional"))
    )
    (net (code "67") (name "Net-(U3-PC4(ADC4{slash}SDA))") (class "Default")
      (node (ref "J10") (pin "5") (pinfunction "5_5") (pintype "passive"))
      (node (ref "U3") (pin "27") (pinfunction "PC4(ADC4/SDA)_27") (pintype "bidirectional"))
    )
    (net (code "68") (name "Net-(U3-PC5(ADC5{slash}SCL))") (class "Default")
      (node (ref "J10") (pin "6") (pinfunction "6_6") (pintype "passive"))
      (node (ref "U3") (pin "28") (pinfunction "PC5(ADC5/SCL)_28") (pintype "bidirectional"))
    )
    (net (code "69") (name "Net-(U3-PD2(INT0))") (class "Default")
      (node (ref "J11") (pin "1") (pinfunction "1_1") (pintype "passive"))
      (node (ref "U3") (pin "32") (pinfunction "PD2(INT0)_32") (pintype "bidirectional"))
    )
    (net (code "70") (name "Net-(U3-PD3(INT1))") (class "Default")
      (node (ref "J11") (pin "2") (pinfunction "2_2") (pintype "passive"))
      (node (ref "U3") (pin "1") (pinfunction "PD3(INT1)_1") (pintype "bidirectional"))
    )
    (net (code "71") (name "Net-(U3-PD4(XCK{slash}T0))") (class "Default")
      (node (ref "J11") (pin "3") (pinfunction "3_3") (pintype "passive"))
      (node (ref "U3") (pin "2") (pinfunction "PD4(XCK/T0)_2") (pintype "bidirectional"))
    )
    (net (code "72") (name "Net-(U3-PD5(T1))") (class "Default")
      (node (ref "J11") (pin "4") (pinfunction "4_4") (pintype "passive"))
      (node (ref "U3") (pin "9") (pinfunction "PD5(T1)_9") (pintype "bidirectional"))
    )
    (net (code "73") (name "Net-(U3-PD6(AIN0))") (class "Default")
      (node (ref "J11") (pin "5") (pinfunction "5_5") (pintype "passive"))
      (node (ref "U3") (pin "10") (pinfunction "PD6(AIN0)_10") (pintype "bidirectional"))
    )
    (net (code "74") (name "Net-(U3-PD7(AIN1))") (class "Default")
      (node (ref "J11") (pin "6") (pinfunction "6_6") (pintype "passive"))
      (node (ref "U3") (pin "11") (pinfunction "PD7(AIN1)_11") (pintype "bidirectional"))
    )
    (net (code "75") (name "RX") (class "Default")
      (node (ref "J9") (pin "RXI") (pinfunction "2_RXI") (pintype "passive"))
      (node (ref "U3") (pin "30") (pinfunction "PD0(RXD)_30") (pintype "bidirectional"))
    )
    (net (code "76") (name "SCK") (class "Default")
      (node (ref "J8") (pin "3") (pinfunction "3_3") (pintype "bidirectional"))
      (node (ref "JP17") (pin "1") (pinfunction "1_1") (pintype "passive"))
      (node (ref "U3") (pin "17") (pinfunction "PB5(SCK)_17") (pintype "bidirectional"))
    )
    (net (code "77") (name "TX") (class "Default")
      (node (ref "J9") (pin "TXO") (pinfunction "3_TXO") (pintype "passive"))
      (node (ref "U3") (pin "31") (pinfunction "PD1(TXD)_31") (pintype "bidirectional"))
    )
    (net (code "78") (name "VDD3V3") (class "Default")
      (node (ref "J5") (pin "2") (pinfunction "2_2") (pintype "bidirectional"))
      (node (ref "J6") (pin "5") (pinfunction "5_5") (pintype "bidirectional"))
      (node (ref "J7") (pin "1") (pinfunction "1_1") (pintype "bidirectional"))
      (node (ref "J7") (pin "2") (pinfunction "2_2") (pintype "bidirectional"))
      (node (ref "JP11") (pin "1") (pinfunction "1_1") (pintype "passive"))
      (node (ref "R6") (pin "2") (pinfunction "2_2") (pintype "passive"))
      (node (ref "U1") (pin "6") (pinfunction "VDD3V3_6") (pintype "power_in"))
      (node (ref "U1") (pin "7") (pinfunction "VDD3V3_7") (pintype "power_in"))
    )
    (net (code "79") (name "VDDAON") (class "Default")
      (node (ref "J7") (pin "3") (pinfunction "3_3") (pintype "bidirectional"))
      (node (ref "J7") (pin "4") (pinfunction "4_4") (pintype "bidirectional"))
      (node (ref "JP13") (pin "1") (pinfunction "1_1") (pintype "passive"))
      (node (ref "U1") (pin "5") (pinfunction "VDDAON_5") (pintype "power_in"))
    )
    (net (code "80") (name "VSS") (class "Default")
      (node (ref "D1") (pin "C") (pinfunction "C_C") (pintype "passive"))
      (node (ref "D2") (pin "C") (pinfunction "C_C") (pintype "passive"))
      (node (ref "D3") (pin "C") (pinfunction "C_C") (pintype "passive"))
      (node (ref "D4") (pin "C") (pinfunction "C_C") (pintype "passive"))
      (node (ref "J5") (pin "6") (pinfunction "6_6") (pintype "bidirectional"))
      (node (ref "J6") (pin "6") (pinfunction "6_6") (pintype "bidirectional"))
      (node (ref "J7") (pin "5") (pinfunction "5_5") (pintype "bidirectional"))
      (node (ref "J7") (pin "6") (pinfunction "6_6") (pintype "bidirectional"))
      (node (ref "JP1") (pin "1") (pinfunction "1_1") (pintype "passive"))
      (node (ref "JP12") (pin "3") (pinfunction "3_3") (pintype "passive"))
      (node (ref "JP6") (pin "2") (pinfunction "2_2") (pintype "passive"))
      (node (ref "U1") (pin "16") (pinfunction "VSS_16") (pintype "power_in"))
      (node (ref "U1") (pin "21") (pinfunction "VSS_21") (pintype "power_in"))
      (node (ref "U1") (pin "23") (pinfunction "VSS_23") (pintype "power_in"))
      (node (ref "U1") (pin "24") (pinfunction "VSS_24") (pintype "power_in"))
      (node (ref "U1") (pin "8") (pinfunction "VSS_8") (pintype "power_in"))
    )
    (net (code "81") (name "V_BAT") (class "Default")
      (node (ref "J4") (pin "1") (pinfunction "1_1") (pintype "passive"))
      (node (ref "J4") (pin "2") (pinfunction "2_2") (pintype "passive"))
      (node (ref "JP9") (pin "1") (pinfunction "1_1") (pintype "passive"))
      (node (ref "S1") (pin "3") (pinfunction "S_3") (pintype "passive"))
    )
    (net (code "82") (name "V_IN") (class "Default")
      (node (ref "C1") (pin "+") (pinfunction "+_+") (pintype "passive"))
      (node (ref "J4") (pin "5") (pinfunction "5_5") (pintype "passive"))
      (node (ref "J4") (pin "6") (pinfunction "6_6") (pintype "passive"))
      (node (ref "JP9") (pin "2") (pinfunction "2_2") (pintype "passive"))
      (node (ref "U2") (pin "1") (pinfunction "IN_1") (pintype "input"))
      (node (ref "U2") (pin "3") (pinfunction "EN_3") (pintype "input"))
    )
    (net (code "83") (name "V_OUT") (class "Default")
      (node (ref "C3") (pin "+") (pinfunction "+_+") (pintype "passive"))
      (node (ref "J4") (pin "7") (pinfunction "7_7") (pintype "passive"))
      (node (ref "J4") (pin "8") (pinfunction "8_8") (pintype "passive"))
      (node (ref "JP10") (pin "1") (pinfunction "1_1") (pintype "passive"))
      (node (ref "U2") (pin "5") (pinfunction "OUT_5") (pintype "passive"))
    )
    (net (code "84") (name "WAKEUP") (class "Default")
      (node (ref "J6") (pin "3") (pinfunction "3_3") (pintype "bidirectional"))
      (node (ref "JP6") (pin "1") (pinfunction "1_1") (pintype "passive"))
      (node (ref "U1") (pin "2") (pinfunction "WAKEUP_2") (pintype "bidirectional"))
    )
    (net (code "85") (name "unconnected-(S1-O-Pad1)") (class "Default")
      (node (ref "S1") (pin "1") (pinfunction "O_1") (pintype "passive"))
    )
    (net (code "86") (name "unconnected-(U4-CS0-Pad9)") (class "Default")
      (node (ref "U4") (pin "9") (pinfunction "CS0_9") (pintype "input"))
    )
    (net (code "87") (name "unconnected-(U4-IO9-Pad11)") (class "Default")
      (node (ref "U4") (pin "11") (pinfunction "IO9_11") (pintype "bidirectional"))
    )
    (net (code "88") (name "unconnected-(U4-IO10-Pad12)") (class "Default")
      (node (ref "U4") (pin "12") (pinfunction "IO10_12") (pintype "bidirectional"))
    )
    (net (code "89") (name "unconnected-(U4-MISO-Pad10)") (class "Default")
      (node (ref "U4") (pin "10") (pinfunction "MISO_10") (pintype "bidirectional"))
    )
    (net (code "90") (name "unconnected-(U4-MOSI-Pad13)") (class "Default")
      (node (ref "U4") (pin "13") (pinfunction "MOSI_13") (pintype "bidirectional"))
    )
    (net (code "91") (name "unconnected-(U4-SCLK-Pad14)") (class "Default")
      (node (ref "U4") (pin "14") (pinfunction "SCLK_14") (pintype "input"))
    )
  )
)
